# psu.net
KiCad netlist of a schematic drawn in EAGLE
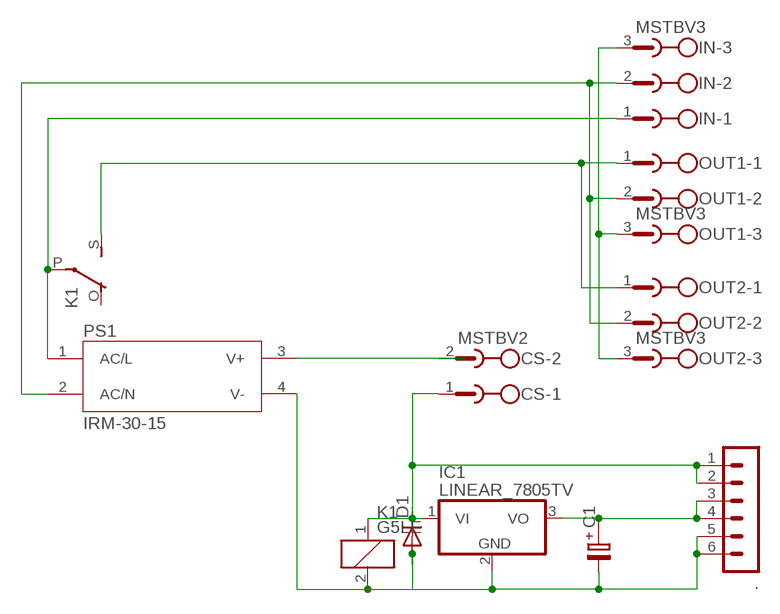
[diagram p0: schematic, sheet 1]

(export (version "E")
  (design (tool "Eeschema 10.0.6"))
  (components
    (comp (ref ".")
      (value "MA06-1")
      (footprint "eagle-import:MA06-1")
      (libsource (lib "eagle-import") (part "MA06-1"))
    )
    (comp (ref "C1")
      (value "C-PR-2,0X5")
      (footprint "eagle-import:E2,0-5")
      (libsource (lib "eagle-import") (part "C-PR-2,0X5"))
    )
    (comp (ref "CS")
      (value "MSTBV2")
      (footprint "eagle-import:MSTBV2")
      (fields (field (name "MPN") "MSTBV 2,5/2-GF-5.08"))
      (libsource (lib "eagle-import") (part "MSTBV2"))
    )
    (comp (ref "D1")
      (value "DIODE-D-2.5")
      (footprint "eagle-import:D-2.5")
      (libsource (lib "eagle-import") (part "DIODE-D-2.5"))
    )
    (comp (ref "IC1")
      (value "LINEAR_7805TV")
      (footprint "eagle-import:LINEAR_TO220V")
      (libsource (lib "eagle-import") (part "LINEAR_78TV05"))
    )
    (comp (ref "IN")
      (value "MSTBV3")
      (footprint "eagle-import:MSTBV3")
      (fields (field (name "MPN") "MSTBV 2,5/3-GF-5.08"))
      (libsource (lib "eagle-import") (part "MSTBV3"))
    )
    (comp (ref "K1")
      (value "G5LE")
      (footprint "eagle-import:G5LE")
      (libsource (lib "eagle-import") (part "G5LE"))
    )
    (comp (ref "OUT1")
      (value "MSTBV3")
      (footprint "eagle-import:MSTBV3")
      (fields (field (name "MPN") "MSTBV 2,5/3-GF-5.08"))
      (libsource (lib "eagle-import") (part "MSTBV3"))
    )
    (comp (ref "OUT2")
      (value "MSTBV3")
      (footprint "eagle-import:MSTBV3")
      (fields (field (name "MPN") "MSTBV 2,5/3-GF-5.08"))
      (libsource (lib "eagle-import") (part "MSTBV3"))
    )
    (comp (ref "PS1")
      (value "IRM-30-15")
      (footprint "eagle-import:CONV_IRM-30-15")
      (fields (field (name "MF") "MEAN WELL"))
      (libsource (lib "eagle-import") (part "IRM-30-15"))
    )
  )
  (nets
    (net (code "1") (name "Net-(CSB-1)") (class "Default")
      (node (ref "CS") (pin "2") (pinfunction "1_2") (pintype "passive"))
      (node (ref "PS1") (pin "3") (pinfunction "V+_3") (pintype "output"))
    )
    (net (code "2") (name "Net-(IC1-GND)") (class "Default")
      (node (ref ".") (pin "5") (pinfunction "5_5") (pintype "passive"))
      (node (ref ".") (pin "6") (pinfunction "6_6") (pintype "passive"))
      (node (ref "C1") (pin "-") (pinfunction "-_-") (pintype "passive"))
      (node (ref "D1") (pin "A") (pinfunction "A_A") (pintype "passive"))
      (node (ref "IC1") (pin "2") (pinfunction "GND_2") (pintype "passive"))
      (node (ref "K1") (pin "2") (pinfunction "2_2") (pintype "passive"))
      (node (ref "PS1") (pin "4") (pinfunction "V-_4") (pintype "output"))
    )
    (net (code "3") (name "Net-(IC1-VI)") (class "Default")
      (node (ref ".") (pin "1") (pinfunction "1_1") (pintype "passive"))
      (node (ref ".") (pin "2") (pinfunction "2_2") (pintype "passive"))
      (node (ref "CS") (pin "1") (pinfunction "1_1") (pintype "passive"))
      (node (ref "D1") (pin "C") (pinfunction "C_C") (pintype "passive"))
      (node (ref "IC1") (pin "1") (pinfunction "VI_1") (pintype "input"))
      (node (ref "K1") (pin "1") (pinfunction "1_1") (pintype "passive"))
    )
    (net (code "4") (name "Net-(IC1-VO)") (class "Default")
      (node (ref ".") (pin "3") (pinfunction "3_3") (pintype "passive"))
      (node (ref ".") (pin "4") (pinfunction "4_4") (pintype "passive"))
      (node (ref "C1") (pin "+") (pinfunction "+_+") (pintype "passive"))
      (node (ref "IC1") (pin "3") (pinfunction "VO_3") (pintype "passive"))
    )
    (net (code "5") (name "Net-(INB-1)") (class "Default")
      (node (ref "IN") (pin "2") (pinfunction "1_2") (pintype "passive"))
      (node (ref "OUT1") (pin "2") (pinfunction "1_2") (pintype "passive"))
      (node (ref "OUT2") (pin "2") (pinfunction "1_2") (pintype "passive"))
      (node (ref "PS1") (pin "2") (pinfunction "AC/N_2") (pintype "input"))
    )
    (net (code "6") (name "Net-(INC-1)") (class "Default")
      (node (ref "IN") (pin "3") (pinfunction "1_3") (pintype "passive"))
      (node (ref "OUT1") (pin "3") (pinfunction "1_3") (pintype "passive"))
      (node (ref "OUT2") (pin "3") (pinfunction "1_3") (pintype "passive"))
    )
    (net (code "7") (name "Net-(K1-PadS)") (class "Default")
      (node (ref "K1") (pin "S") (pinfunction "S_S") (pintype "passive"))
      (node (ref "OUT1") (pin "1") (pinfunction "1_1") (pintype "passive"))
      (node (ref "OUT2") (pin "1") (pinfunction "1_1") (pintype "passive"))
    )
    (net (code "8") (name "Net-(PS1-AC{slash}L)") (class "Default")
      (node (ref "IN") (pin "1") (pinfunction "1_1") (pintype "passive"))
      (node (ref "K1") (pin "P") (pinfunction "P_P") (pintype "passive"))
      (node (ref "PS1") (pin "1") (pinfunction "AC/L_1") (pintype "input"))
    )
    (net (code "9") (name "unconnected-(K1-PadO)") (class "Default")
      (node (ref "K1") (pin "O") (pinfunction "O_O") (pintype "passive"))
    )
  )
)
